# cpu.net
KiCad netlist of a schematic drawn in Altium Designer
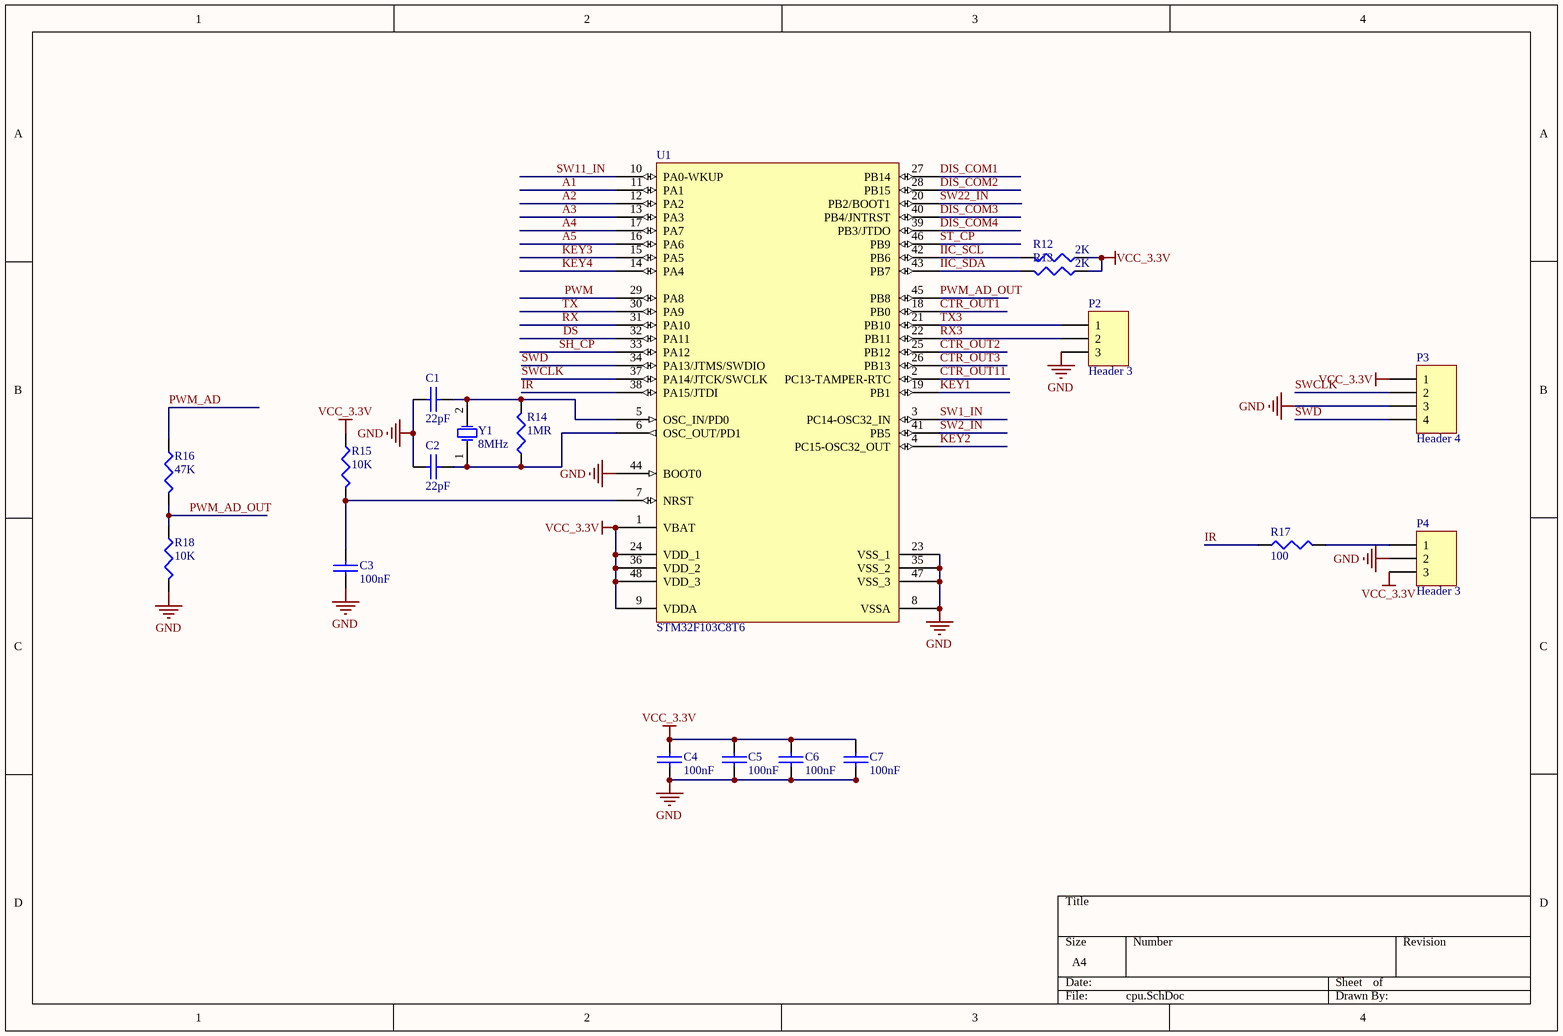
[diagram p0: cpu.SchDoc]

(export (version "E")
  (design (tool "Eeschema 10.0.6"))
  (components
    (comp (ref "C1")
      (value "22pF")
      (footprint "0805c")
      (description "Capacitor")
      (libsource (lib "SM") (part "CAP"))
    )
    (comp (ref "C2")
      (value "22pF")
      (footprint "0805c")
      (description "Capacitor")
      (libsource (lib "SM") (part "CAP"))
    )
    (comp (ref "C3")
      (value "100nF")
      (footprint "0805c")
      (description "Capacitor")
      (libsource (lib "SM") (part "CAP"))
    )
    (comp (ref "C4")
      (value "100nF")
      (footprint "0805c")
      (description "Capacitor")
      (libsource (lib "SM") (part "CAP"))
    )
    (comp (ref "C5")
      (value "100nF")
      (footprint "0805c")
      (description "Capacitor")
      (libsource (lib "SM") (part "CAP"))
    )
    (comp (ref "C6")
      (value "100nF")
      (footprint "0805c")
      (description "Capacitor")
      (libsource (lib "SM") (part "CAP"))
    )
    (comp (ref "C7")
      (value "100nF")
      (footprint "0805c")
      (description "Capacitor")
      (libsource (lib "SM") (part "CAP"))
    )
    (comp (ref "P2")
      (value "Header 3")
      (footprint "HDR1X3")
      (description "Header, 3-Pin")
      (fields (field (name "PUBLISHER") "Altium Limited"))
      (libsource (lib "Miscellaneous Connectors") (part "Header 3"))
    )
    (comp (ref "P3")
      (value "Header 4")
      (footprint "HDR1X4")
      (description "Header, 4-Pin")
      (fields (field (name "PUBLISHER") "Altium Limited"))
      (libsource (lib "Miscellaneous Connectors") (part "Header 4"))
    )
    (comp (ref "P4")
      (value "Header 3")
      (footprint "HDR1X3")
      (description "Header, 3-Pin")
      (fields (field (name "PUBLISHER") "Altium Limited"))
      (libsource (lib "Miscellaneous Connectors") (part "Header 3"))
    )
    (comp (ref "R12")
      (value "2K")
      (footprint "0805R")
      (description "Resistor")
      (fields (field (name "PUBLISHER") "Altium Limited"))
      (libsource (lib "SM") (part "Res3"))
    )
    (comp (ref "R13")
      (value "2K")
      (footprint "0805R")
      (description "Resistor")
      (fields (field (name "PUBLISHER") "Altium Limited"))
      (libsource (lib "SM") (part "Res3"))
    )
    (comp (ref "R14")
      (value "1MR")
      (footprint "0805R")
      (description "Resistor")
      (fields (field (name "PUBLISHER") "Altium Limited"))
      (libsource (lib "SM") (part "Res3"))
    )
    (comp (ref "R15")
      (value "10K")
      (footprint "0805R")
      (description "Resistor")
      (fields (field (name "PUBLISHER") "Altium Limited"))
      (libsource (lib "SM") (part "Res3"))
    )
    (comp (ref "R16")
      (value "47K")
      (footprint "0805R")
      (description "Resistor")
      (fields (field (name "PUBLISHER") "Altium Limited"))
      (libsource (lib "SM") (part "Res3"))
    )
    (comp (ref "R17")
      (value "100")
      (footprint "0805R")
      (description "Resistor")
      (fields (field (name "PUBLISHER") "Altium Limited"))
      (libsource (lib "SM") (part "Res3"))
    )
    (comp (ref "R18")
      (value "10K")
      (footprint "0805R")
      (description "Resistor")
      (fields (field (name "PUBLISHER") "Altium Limited"))
      (libsource (lib "SM") (part "Res3"))
    )
    (comp (ref "U1")
      (value "STM32F103C8T6")
      (footprint "TQFP-48")
      (description "STM32 ARM-based 32-bit MCU with 64 Kbytes Flash, 48-pin LQFP, Industrial Temperature")
      (fields (field (name "PUBLISHER") "Altium Limited"))
      (libsource (lib "ST Microcontroller 32-Bit STM32") (part "STM32F103C8T6"))
    )
    (comp (ref "Y1")
      (value "8MHz")
      (footprint "SMT5032")
      (description "Crystal Oscillator")
      (fields (field (name "PUBLISHER") "Altium Limited"))
      (libsource (lib "Miscellaneous Devices") (part "XTAL"))
    )
  )
  (nets
    (net (code "1") (name "/A1") (class "Default")
      (node (ref "U1") (pin "11") (pinfunction "PA1_11") (pintype "bidirectional"))
    )
    (net (code "2") (name "/A2") (class "Default")
      (node (ref "U1") (pin "12") (pinfunction "PA2_12") (pintype "bidirectional"))
    )
    (net (code "3") (name "/A3") (class "Default")
      (node (ref "U1") (pin "13") (pinfunction "PA3_13") (pintype "bidirectional"))
    )
    (net (code "4") (name "/A4") (class "Default")
      (node (ref "U1") (pin "17") (pinfunction "PA7_17") (pintype "bidirectional"))
    )
    (net (code "5") (name "/A5") (class "Default")
      (node (ref "U1") (pin "16") (pinfunction "PA6_16") (pintype "bidirectional"))
    )
    (net (code "6") (name "/CTR_OUT1") (class "Default")
      (node (ref "U1") (pin "18") (pinfunction "PB0_18") (pintype "bidirectional"))
    )
    (net (code "7") (name "/CTR_OUT2") (class "Default")
      (node (ref "U1") (pin "25") (pinfunction "PB12_25") (pintype "bidirectional"))
    )
    (net (code "8") (name "/CTR_OUT3") (class "Default")
      (node (ref "U1") (pin "26") (pinfunction "PB13_26") (pintype "bidirectional"))
    )
    (net (code "9") (name "/CTR_OUT11") (class "Default")
      (node (ref "U1") (pin "2") (pinfunction "PC13-TAMPER-RTC_2") (pintype "bidirectional"))
    )
    (net (code "10") (name "/DIS_COM1") (class "Default")
      (node (ref "U1") (pin "27") (pinfunction "PB14_27") (pintype "bidirectional"))
    )
    (net (code "11") (name "/DIS_COM2") (class "Default")
      (node (ref "U1") (pin "28") (pinfunction "PB15_28") (pintype "bidirectional"))
    )
    (net (code "12") (name "/DIS_COM3") (class "Default")
      (node (ref "U1") (pin "40") (pinfunction "PB4/JNTRST_40") (pintype "bidirectional"))
    )
    (net (code "13") (name "/DIS_COM4") (class "Default")
      (node (ref "U1") (pin "39") (pinfunction "PB3/JTDO_39") (pintype "bidirectional"))
    )
    (net (code "14") (name "/DS") (class "Default")
      (node (ref "U1") (pin "32") (pinfunction "PA11_32") (pintype "bidirectional"))
    )
    (net (code "15") (name "/IIC_SCL") (class "Default")
      (node (ref "R12") (pin "2") (pinfunction "2_2") (pintype "passive"))
      (node (ref "U1") (pin "42") (pinfunction "PB6_42") (pintype "bidirectional"))
    )
    (net (code "16") (name "/IIC_SDA") (class "Default")
      (node (ref "R13") (pin "2") (pinfunction "2_2") (pintype "passive"))
      (node (ref "U1") (pin "43") (pinfunction "PB7_43") (pintype "bidirectional"))
    )
    (net (code "17") (name "/IR") (class "Default")
      (node (ref "R17") (pin "1") (pinfunction "1_1") (pintype "passive"))
      (node (ref "U1") (pin "38") (pinfunction "PA15/JTDI_38") (pintype "bidirectional"))
    )
    (net (code "18") (name "/KEY1") (class "Default")
      (node (ref "U1") (pin "19") (pinfunction "PB1_19") (pintype "bidirectional"))
    )
    (net (code "19") (name "/KEY2") (class "Default")
      (node (ref "U1") (pin "4") (pinfunction "PC15-OSC32_OUT_4") (pintype "bidirectional"))
    )
    (net (code "20") (name "/KEY3") (class "Default")
      (node (ref "U1") (pin "15") (pinfunction "PA5_15") (pintype "bidirectional"))
    )
    (net (code "21") (name "/KEY4") (class "Default")
      (node (ref "U1") (pin "14") (pinfunction "PA4_14") (pintype "bidirectional"))
    )
    (net (code "22") (name "/PWM") (class "Default")
      (node (ref "U1") (pin "29") (pinfunction "PA8_29") (pintype "bidirectional"))
    )
    (net (code "23") (name "/PWM_AD") (class "Default")
      (node (ref "R16") (pin "1") (pinfunction "1_1") (pintype "passive"))
    )
    (net (code "24") (name "/PWM_AD_OUT") (class "Default")
      (node (ref "R16") (pin "2") (pinfunction "2_2") (pintype "passive"))
      (node (ref "R18") (pin "1") (pinfunction "1_1") (pintype "passive"))
      (node (ref "U1") (pin "45") (pinfunction "PB8_45") (pintype "bidirectional"))
    )
    (net (code "25") (name "/RX") (class "Default")
      (node (ref "U1") (pin "31") (pinfunction "PA10_31") (pintype "bidirectional"))
    )
    (net (code "26") (name "/RX3") (class "Default")
      (node (ref "P2") (pin "2") (pinfunction "2_2") (pintype "passive"))
      (node (ref "U1") (pin "22") (pinfunction "PB11_22") (pintype "bidirectional"))
    )
    (net (code "27") (name "/SH_CP") (class "Default")
      (node (ref "U1") (pin "33") (pinfunction "PA12_33") (pintype "bidirectional"))
    )
    (net (code "28") (name "/ST_CP") (class "Default")
      (node (ref "U1") (pin "46") (pinfunction "PB9_46") (pintype "bidirectional"))
    )
    (net (code "29") (name "/SW1_IN") (class "Default")
      (node (ref "U1") (pin "3") (pinfunction "PC14-OSC32_IN_3") (pintype "bidirectional"))
    )
    (net (code "30") (name "/SW2_IN") (class "Default")
      (node (ref "U1") (pin "41") (pinfunction "PB5_41") (pintype "bidirectional"))
    )
    (net (code "31") (name "/SW11_IN") (class "Default")
      (node (ref "U1") (pin "10") (pinfunction "PA0-WKUP_10") (pintype "bidirectional"))
    )
    (net (code "32") (name "/SW22_IN") (class "Default")
      (node (ref "U1") (pin "20") (pinfunction "PB2/BOOT1_20") (pintype "bidirectional"))
    )
    (net (code "33") (name "/SWCLK") (class "Default")
      (node (ref "P3") (pin "2") (pinfunction "2_2") (pintype "passive"))
      (node (ref "U1") (pin "37") (pinfunction "PA14/JTCK/SWCLK_37") (pintype "bidirectional"))
    )
    (net (code "34") (name "/SWD") (class "Default")
      (node (ref "P3") (pin "4") (pinfunction "4_4") (pintype "passive"))
      (node (ref "U1") (pin "34") (pinfunction "PA13/JTMS/SWDIO_34") (pintype "bidirectional"))
    )
    (net (code "35") (name "/TX") (class "Default")
      (node (ref "U1") (pin "30") (pinfunction "PA9_30") (pintype "bidirectional"))
    )
    (net (code "36") (name "/TX3") (class "Default")
      (node (ref "P2") (pin "1") (pinfunction "1_1") (pintype "passive"))
      (node (ref "U1") (pin "21") (pinfunction "PB10_21") (pintype "bidirectional"))
    )
    (net (code "37") (name "GND") (class "Default")
      (node (ref "C1") (pin "1") (pinfunction "1_1") (pintype "passive"))
      (node (ref "C2") (pin "1") (pinfunction "1_1") (pintype "passive"))
      (node (ref "C3") (pin "1") (pinfunction "1_1") (pintype "passive"))
      (node (ref "C4") (pin "1") (pinfunction "1_1") (pintype "passive"))
      (node (ref "C5") (pin "1") (pinfunction "1_1") (pintype "passive"))
      (node (ref "C6") (pin "1") (pinfunction "1_1") (pintype "passive"))
      (node (ref "C7") (pin "1") (pinfunction "1_1") (pintype "passive"))
      (node (ref "P2") (pin "3") (pinfunction "3_3") (pintype "passive"))
      (node (ref "P3") (pin "3") (pinfunction "3_3") (pintype "passive"))
      (node (ref "P4") (pin "2") (pinfunction "2_2") (pintype "passive"))
      (node (ref "R18") (pin "2") (pinfunction "2_2") (pintype "passive"))
      (node (ref "U1") (pin "23") (pinfunction "VSS_1_23") (pintype "power_in"))
      (node (ref "U1") (pin "35") (pinfunction "VSS_2_35") (pintype "power_in"))
      (node (ref "U1") (pin "44") (pinfunction "BOOT0_44") (pintype "input"))
      (node (ref "U1") (pin "47") (pinfunction "VSS_3_47") (pintype "power_in"))
      (node (ref "U1") (pin "8") (pinfunction "VSSA_8") (pintype "power_in"))
    )
    (net (code "38") (name "Net-(P4-Pad1)") (class "Default")
      (node (ref "P4") (pin "1") (pinfunction "1_1") (pintype "passive"))
      (node (ref "R17") (pin "2") (pinfunction "2_2") (pintype "passive"))
    )
    (net (code "39") (name "Net-(U1-NRST)") (class "Default")
      (node (ref "C3") (pin "2") (pinfunction "2_2") (pintype "passive"))
      (node (ref "R15") (pin "2") (pinfunction "2_2") (pintype "passive"))
      (node (ref "U1") (pin "7") (pinfunction "NRST_7") (pintype "bidirectional"))
    )
    (net (code "40") (name "Net-(U1-OSC_IN{slash}PD0)") (class "Default")
      (node (ref "C1") (pin "2") (pinfunction "2_2") (pintype "passive"))
      (node (ref "R14") (pin "2") (pinfunction "2_2") (pintype "passive"))
      (node (ref "U1") (pin "5") (pinfunction "OSC_IN/PD0_5") (pintype "input"))
      (node (ref "Y1") (pin "2") (pinfunction "OSC2_2") (pintype "passive"))
    )
    (net (code "41") (name "Net-(U1-OSC_OUT{slash}PD1)") (class "Default")
      (node (ref "C2") (pin "2") (pinfunction "2_2") (pintype "passive"))
      (node (ref "R14") (pin "1") (pinfunction "1_1") (pintype "passive"))
      (node (ref "U1") (pin "6") (pinfunction "OSC_OUT/PD1_6") (pintype "output"))
      (node (ref "Y1") (pin "1") (pinfunction "OSC1_1") (pintype "passive"))
    )
    (net (code "42") (name "VCC_3.3V") (class "Default")
      (node (ref "C4") (pin "2") (pinfunction "2_2") (pintype "passive"))
      (node (ref "C5") (pin "2") (pinfunction "2_2") (pintype "passive"))
      (node (ref "C6") (pin "2") (pinfunction "2_2") (pintype "passive"))
      (node (ref "C7") (pin "2") (pinfunction "2_2") (pintype "passive"))
      (node (ref "P3") (pin "1") (pinfunction "1_1") (pintype "passive"))
      (node (ref "P4") (pin "3") (pinfunction "3_3") (pintype "passive"))
      (node (ref "R12") (pin "1") (pinfunction "1_1") (pintype "passive"))
      (node (ref "R13") (pin "1") (pinfunction "1_1") (pintype "passive"))
      (node (ref "R15") (pin "1") (pinfunction "1_1") (pintype "passive"))
      (node (ref "U1") (pin "1") (pinfunction "VBAT_1") (pintype "power_in"))
      (node (ref "U1") (pin "24") (pinfunction "VDD_1_24") (pintype "power_in"))
      (node (ref "U1") (pin "36") (pinfunction "VDD_2_36") (pintype "power_in"))
      (node (ref "U1") (pin "48") (pinfunction "VDD_3_48") (pintype "power_in"))
      (node (ref "U1") (pin "9") (pinfunction "VDDA_9") (pintype "power_in"))
    )
  )
)
